# OnOnfre_dual_parafuso_ssr.net
KiCad netlist of a schematic drawn in EAGLE
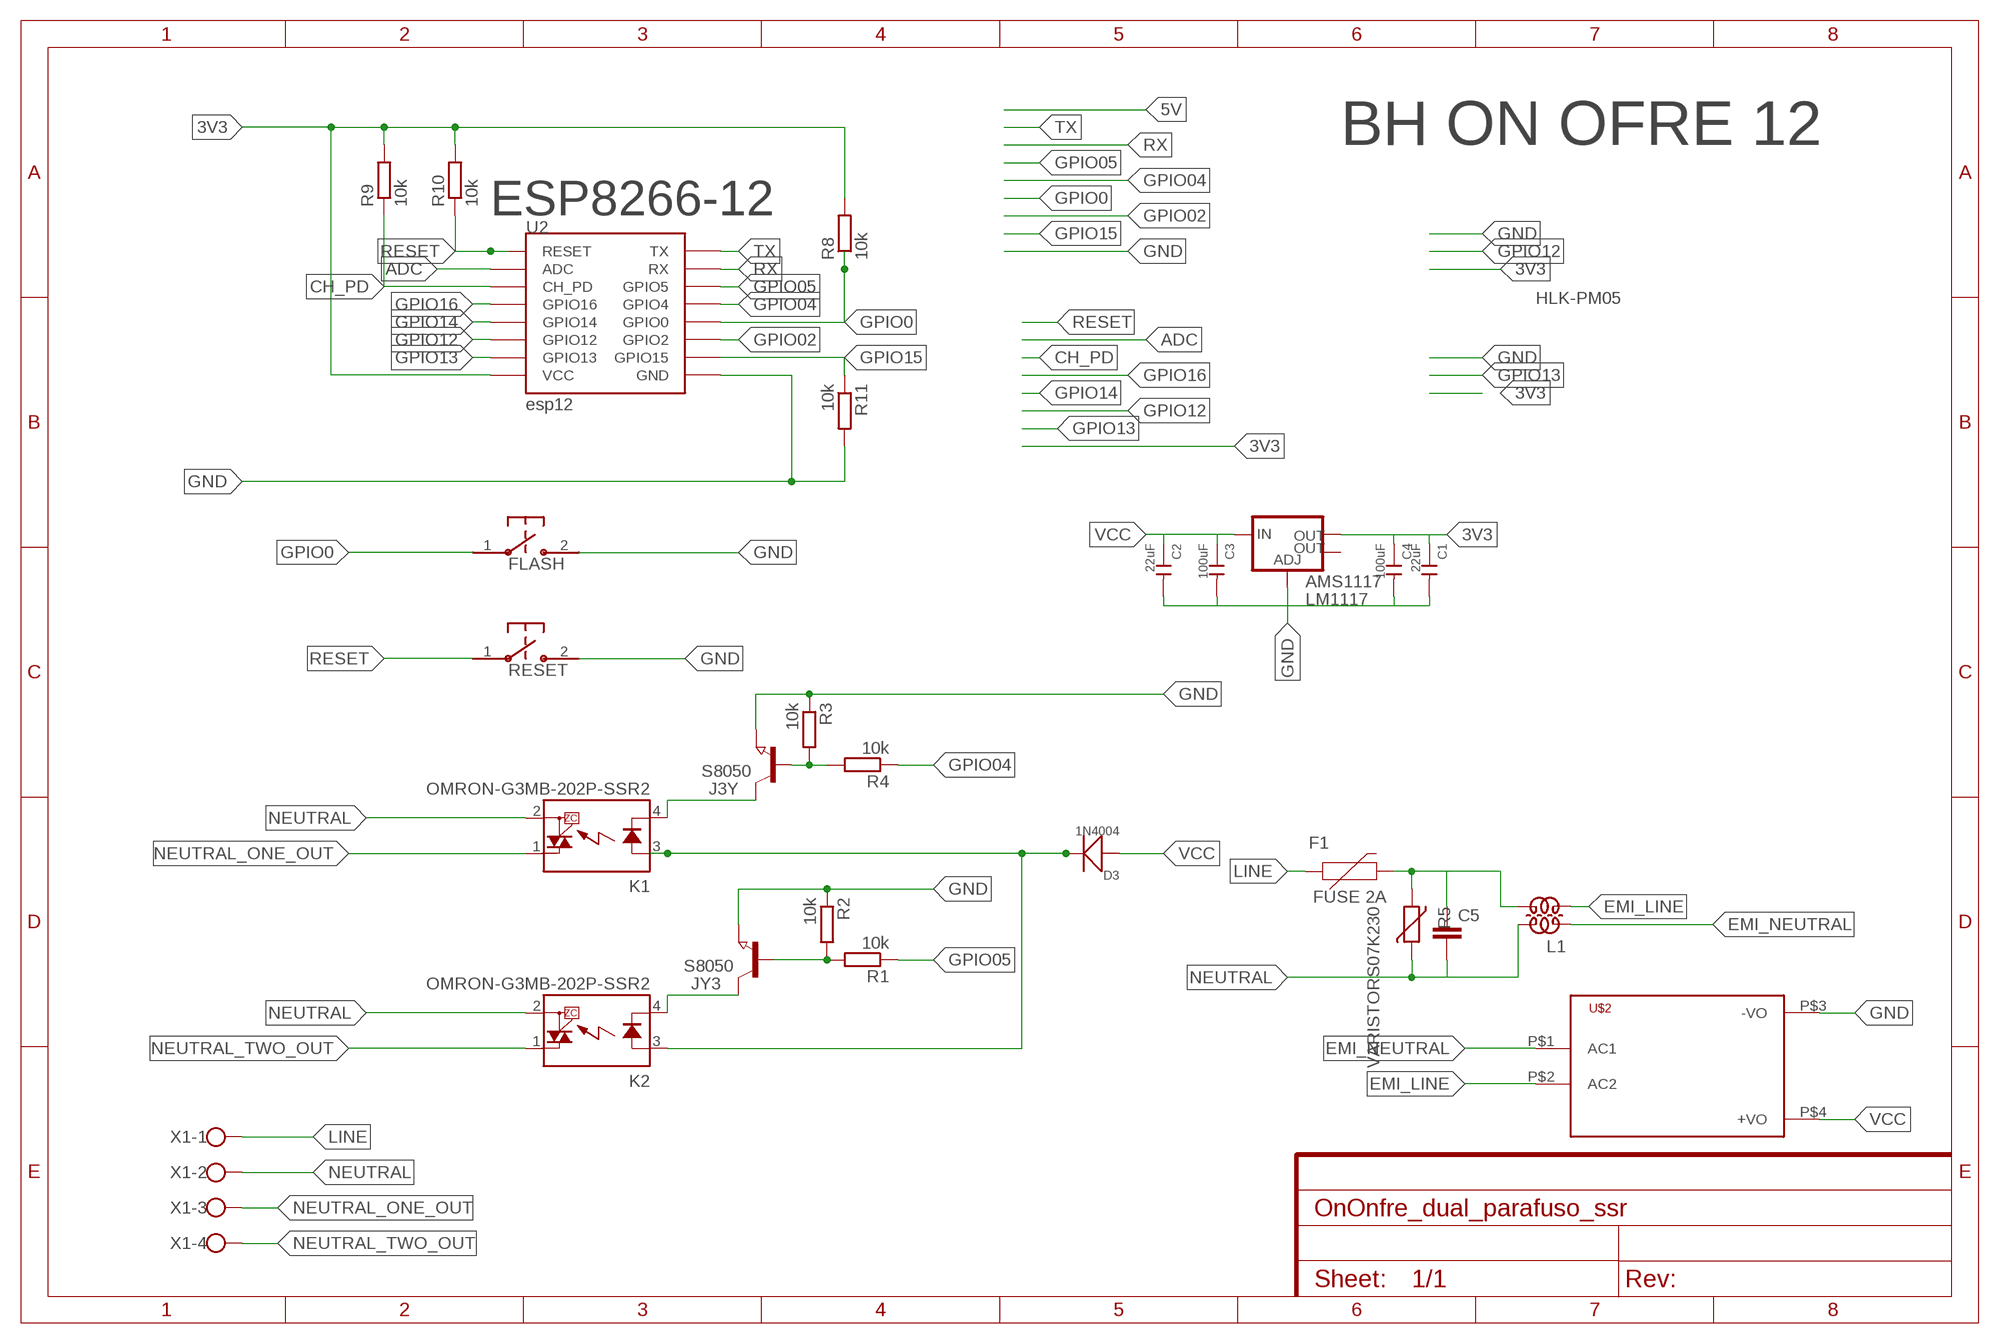
[diagram p0: schematic, sheet 1]

(export (version "E")
  (design (tool "Eeschema 10.0.6"))
  (components
    (comp (ref "AMS1117")
      (value "LM1117")
      (footprint "eagle-import:SOT223")
      (libsource (lib "eagle-import") (part "V_REG_LM1117SOT223"))
    )
    (comp (ref "C1")
      (value "22uF")
      (footprint "eagle-import:C1206")
      (fields (field (name "MPN") "CC1206KKX7RCBB102"))
      (libsource (lib "eagle-import") (part "CERAMIC-1NF-1KV-10%-X7R?(1206)"))
    )
    (comp (ref "C2")
      (value "22uF")
      (footprint "eagle-import:C1206")
      (fields (field (name "MPN") "CC1206KKX7RCBB102"))
      (libsource (lib "eagle-import") (part "CERAMIC-1NF-1KV-10%-X7R?(1206)"))
    )
    (comp (ref "C3")
      (value "100uF")
      (footprint "eagle-import:C1206")
      (fields (field (name "MPN") "CC1206KKX7RCBB102"))
      (libsource (lib "eagle-import") (part "CERAMIC-1NF-1KV-10%-X7R?(1206)"))
    )
    (comp (ref "C4")
      (value "100uF")
      (footprint "eagle-import:C1206")
      (fields (field (name "MPN") "CC1206KKX7RCBB102"))
      (libsource (lib "eagle-import") (part "CERAMIC-1NF-1KV-10%-X7R?(1206)"))
    )
    (comp (ref "C5")
      (value "C-EU102-054X133")
      (footprint "eagle-import:C102-054X133")
      (libsource (lib "eagle-import") (part "C-EU102-054X133"))
    )
    (comp (ref "D3")
      (value "1N4004")
      (footprint "eagle-import:DO-214AC")
      (fields (field (name "MPN") "1N4007"))
      (libsource (lib "eagle-import") (part "DIODE-GEN-PURPOSE-1KV-1A(DO-214AC)"))
    )
    (comp (ref "F1")
      (value "FUSE 2A")
      (footprint "eagle-import:PTH")
      (libsource (lib "eagle-import") (part "PPTC_PTH"))
    )
    (comp (ref "FLASH")
      (value "B3U-1000P-2P-SMD")
      (footprint "eagle-import:B3U-1000P")
      (fields (field (name "MANUFACTURER") "Omron") (field (name "MPN") "B3U-1000P"))
      (libsource (lib "eagle-import") (part "B3U-1000P"))
    )
    (comp (ref "J3Y")
      (value "S8050")
      (footprint "eagle-import:SOT23")
      (libsource (lib "eagle-import") (part "NPN-TRANSISTOR_SOT23"))
    )
    (comp (ref "JY3")
      (value "S8050")
      (footprint "eagle-import:SOT23")
      (libsource (lib "eagle-import") (part "NPN-TRANSISTOR_SOT23"))
    )
    (comp (ref "K1")
      (value "OMRON-G3MB-202P-SSR2")
      (footprint "eagle-import:OMRON-G3MB-202P-SSR")
      (fields (field (name "MPN") "S202S02F"))
      (libsource (lib "eagle-import") (part "OMRON-G3MB-202P-SSR2"))
    )
    (comp (ref "K2")
      (value "OMRON-G3MB-202P-SSR2")
      (footprint "eagle-import:OMRON-G3MB-202P-SSR")
      (fields (field (name "MPN") "S202S02F"))
      (libsource (lib "eagle-import") (part "OMRON-G3MB-202P-SSR2"))
    )
    (comp (ref "L1")
      (value "ZD60820510")
      (footprint "eagle-import:ZD6-2X15")
      (libsource (lib "eagle-import") (part "ZD60820510"))
    )
    (comp (ref "R1")
      (value "10k")
      (footprint "eagle-import:R0603")
      (libsource (lib "eagle-import") (part "R-EU_R0603"))
    )
    (comp (ref "R2")
      (value "10k")
      (footprint "eagle-import:R0603")
      (libsource (lib "eagle-import") (part "R-EU_R0603"))
    )
    (comp (ref "R3")
      (value "10k")
      (footprint "eagle-import:R0603")
      (libsource (lib "eagle-import") (part "R-EU_R0603"))
    )
    (comp (ref "R4")
      (value "10k")
      (footprint "eagle-import:R0603")
      (libsource (lib "eagle-import") (part "R-EU_R0603"))
    )
    (comp (ref "R5")
      (value "VARISTORS07K230")
      (footprint "eagle-import:S07K230")
      (libsource (lib "eagle-import") (part "VARISTORS07K230"))
    )
    (comp (ref "R8")
      (value "10k")
      (footprint "eagle-import:R0603")
      (libsource (lib "eagle-import") (part "R-EU_R0603"))
    )
    (comp (ref "R9")
      (value "10k")
      (footprint "eagle-import:R0603")
      (libsource (lib "eagle-import") (part "R-EU_R0603"))
    )
    (comp (ref "R10")
      (value "10k")
      (footprint "eagle-import:R0603")
      (libsource (lib "eagle-import") (part "R-EU_R0603"))
    )
    (comp (ref "R11")
      (value "10k")
      (footprint "eagle-import:R0603")
      (libsource (lib "eagle-import") (part "R-EU_R0603"))
    )
    (comp (ref "RESET")
      (value "B3U-1000P-2P-SMD")
      (footprint "eagle-import:B3U-1000P")
      (fields (field (name "MANUFACTURER") "Omron") (field (name "MPN") "B3U-1000P"))
      (libsource (lib "eagle-import") (part "B3U-1000P"))
    )
    (comp (ref "U$2")
      (value "HKLPM01")
      (footprint "eagle-import:HKLPM01")
      (libsource (lib "eagle-import") (part "HKLPM01"))
    )
    (comp (ref "U2")
      (value "esp12")
      (footprint "eagle-import:ESP12-SMD")
      (libsource (lib "eagle-import") (part "ESP12SMD"))
    )
    (comp (ref "X1")
      (value "W237-4")
      (footprint "eagle-import:W237-4")
      (libsource (lib "eagle-import") (part "W237-4"))
    )
  )
  (nets
    (net (code "1") (name "3V3") (class "Default")
      (node (ref "AMS1117") (pin "2") (pinfunction "OUT_2") (pintype "output"))
      (node (ref "C1") (pin "1") (pinfunction "1_1") (pintype "passive"))
      (node (ref "C4") (pin "1") (pinfunction "1_1") (pintype "passive"))
      (node (ref "R10") (pin "2") (pinfunction "2_2") (pintype "passive"))
      (node (ref "R8") (pin "2") (pinfunction "2_2") (pintype "passive"))
      (node (ref "R9") (pin "2") (pinfunction "2_2") (pintype "passive"))
      (node (ref "U2") (pin "VCC") (pinfunction "VCC_VCC") (pintype "bidirectional"))
    )
    (net (code "2") (name "5V") (class "Default")
      (node (ref "D3") (pin "2") (pinfunction "-_2") (pintype "passive"))
      (node (ref "K1") (pin "3") (pinfunction "A_3") (pintype "passive"))
      (node (ref "K2") (pin "3") (pinfunction "A_3") (pintype "passive"))
    )
    (net (code "3") (name "ADC") (class "Default")
      (node (ref "U2") (pin "ADC") (pinfunction "ADC_ADC") (pintype "bidirectional"))
    )
    (net (code "4") (name "CH_PD") (class "Default")
      (node (ref "R9") (pin "1") (pinfunction "1_1") (pintype "passive"))
      (node (ref "U2") (pin "CH_PD") (pinfunction "CH_PD_CH_PD") (pintype "bidirectional"))
    )
    (net (code "5") (name "EMI_LINE") (class "Default")
      (node (ref "L1") (pin "2") (pinfunction "2_2") (pintype "passive"))
      (node (ref "U$2") (pin "P$2") (pinfunction "AC2_P$2") (pintype "bidirectional"))
    )
    (net (code "6") (name "EMI_NEUTRAL") (class "Default")
      (node (ref "L1") (pin "1") (pinfunction "1_1") (pintype "passive"))
      (node (ref "U$2") (pin "P$1") (pinfunction "AC1_P$1") (pintype "bidirectional"))
    )
    (net (code "7") (name "GND") (class "Default")
      (node (ref "AMS1117") (pin "1") (pinfunction "ADJ_1") (pintype "input"))
      (node (ref "C1") (pin "2") (pinfunction "2_2") (pintype "passive"))
      (node (ref "C2") (pin "2") (pinfunction "2_2") (pintype "passive"))
      (node (ref "C3") (pin "2") (pinfunction "2_2") (pintype "passive"))
      (node (ref "C4") (pin "2") (pinfunction "2_2") (pintype "passive"))
      (node (ref "FLASH") (pin "2") (pinfunction "P$2_2") (pintype "passive"))
      (node (ref "J3Y") (pin "2") (pinfunction "E_2") (pintype "passive"))
      (node (ref "JY3") (pin "2") (pinfunction "E_2") (pintype "passive"))
      (node (ref "R11") (pin "2") (pinfunction "2_2") (pintype "passive"))
      (node (ref "R2") (pin "1") (pinfunction "1_1") (pintype "passive"))
      (node (ref "R3") (pin "1") (pinfunction "1_1") (pintype "passive"))
      (node (ref "RESET") (pin "2") (pinfunction "P$2_2") (pintype "passive"))
      (node (ref "U$2") (pin "P$3") (pinfunction "-VO_P$3") (pintype "bidirectional"))
      (node (ref "U2") (pin "GND") (pinfunction "GND_GND") (pintype "bidirectional"))
    )
    (net (code "8") (name "GPIO0") (class "Default")
      (node (ref "FLASH") (pin "1") (pinfunction "P$1_1") (pintype "passive"))
      (node (ref "R8") (pin "1") (pinfunction "1_1") (pintype "passive"))
      (node (ref "U2") (pin "GPIO0") (pinfunction "GPIO0_GPIO0") (pintype "bidirectional"))
    )
    (net (code "9") (name "GPIO02") (class "Default")
      (node (ref "U2") (pin "GPIO2") (pinfunction "GPIO2_GPIO2") (pintype "bidirectional"))
    )
    (net (code "10") (name "GPIO04") (class "Default")
      (node (ref "R4") (pin "1") (pinfunction "1_1") (pintype "passive"))
      (node (ref "U2") (pin "GPIO4") (pinfunction "GPIO4_GPIO4") (pintype "bidirectional"))
    )
    (net (code "11") (name "GPIO05") (class "Default")
      (node (ref "R1") (pin "1") (pinfunction "1_1") (pintype "passive"))
      (node (ref "U2") (pin "GPIO5") (pinfunction "GPIO5_GPIO5") (pintype "bidirectional"))
    )
    (net (code "12") (name "GPIO12") (class "Default")
      (node (ref "U2") (pin "GPIO12") (pinfunction "GPIO12_GPIO12") (pintype "bidirectional"))
    )
    (net (code "13") (name "GPIO13") (class "Default")
      (node (ref "U2") (pin "GPIO13") (pinfunction "GPIO13_GPIO13") (pintype "bidirectional"))
    )
    (net (code "14") (name "GPIO14") (class "Default")
      (node (ref "U2") (pin "GPIO14") (pinfunction "GPIO14_GPIO14") (pintype "bidirectional"))
    )
    (net (code "15") (name "GPIO15") (class "Default")
      (node (ref "R11") (pin "1") (pinfunction "1_1") (pintype "passive"))
      (node (ref "U2") (pin "GPIO15") (pinfunction "GPIO15_GPIO15") (pintype "bidirectional"))
    )
    (net (code "16") (name "GPIO16") (class "Default")
      (node (ref "U2") (pin "GPIO16") (pinfunction "GPIO16_GPIO16") (pintype "bidirectional"))
    )
    (net (code "17") (name "LINE") (class "Default")
      (node (ref "F1") (pin "P$1") (pinfunction "1_P$1") (pintype "bidirectional"))
      (node (ref "X1") (pin "1") (pinfunction "KL_1") (pintype "passive"))
    )
    (net (code "18") (name "NEUTRAL") (class "Default")
      (node (ref "C5") (pin "2") (pinfunction "2_2") (pintype "passive"))
      (node (ref "K1") (pin "2") (pinfunction "DS2_2") (pintype "passive"))
      (node (ref "K2") (pin "2") (pinfunction "DS2_2") (pintype "passive"))
      (node (ref "L1") (pin "4") (pinfunction "4_4") (pintype "passive"))
      (node (ref "R5") (pin "1") (pinfunction "1_1") (pintype "passive"))
      (node (ref "X1") (pin "2") (pinfunction "KL_2") (pintype "passive"))
    )
    (net (code "19") (name "NEUTRAL_ONE_OUT") (class "Default")
      (node (ref "K1") (pin "1") (pinfunction "DS1_1") (pintype "passive"))
      (node (ref "X1") (pin "3") (pinfunction "KL_3") (pintype "passive"))
    )
    (net (code "20") (name "NEUTRAL_TWO_OUT") (class "Default")
      (node (ref "K2") (pin "1") (pinfunction "DS1_1") (pintype "passive"))
      (node (ref "X1") (pin "4") (pinfunction "KL_4") (pintype "passive"))
    )
    (net (code "21") (name "Net-(F1-2)") (class "Default")
      (node (ref "C5") (pin "1") (pinfunction "1_1") (pintype "passive"))
      (node (ref "F1") (pin "P$2") (pinfunction "2_P$2") (pintype "bidirectional"))
      (node (ref "L1") (pin "3") (pinfunction "3_3") (pintype "passive"))
      (node (ref "R5") (pin "2") (pinfunction "2_2") (pintype "passive"))
    )
    (net (code "22") (name "Net-(J3Y-B)") (class "Default")
      (node (ref "J3Y") (pin "1") (pinfunction "B_1") (pintype "passive"))
      (node (ref "R3") (pin "2") (pinfunction "2_2") (pintype "passive"))
      (node (ref "R4") (pin "2") (pinfunction "2_2") (pintype "passive"))
    )
    (net (code "23") (name "Net-(J3Y-C)") (class "Default")
      (node (ref "J3Y") (pin "3") (pinfunction "C_3") (pintype "passive"))
      (node (ref "K1") (pin "4") (pinfunction "K_4") (pintype "passive"))
    )
    (net (code "24") (name "Net-(JY3-B)") (class "Default")
      (node (ref "JY3") (pin "1") (pinfunction "B_1") (pintype "passive"))
      (node (ref "R1") (pin "2") (pinfunction "2_2") (pintype "passive"))
      (node (ref "R2") (pin "2") (pinfunction "2_2") (pintype "passive"))
    )
    (net (code "25") (name "Net-(JY3-C)") (class "Default")
      (node (ref "JY3") (pin "3") (pinfunction "C_3") (pintype "passive"))
      (node (ref "K2") (pin "4") (pinfunction "K_4") (pintype "passive"))
    )
    (net (code "26") (name "RESET") (class "Default")
      (node (ref "R10") (pin "1") (pinfunction "1_1") (pintype "passive"))
      (node (ref "RESET") (pin "1") (pinfunction "P$1_1") (pintype "passive"))
      (node (ref "U2") (pin "RESET") (pinfunction "RESET_RESET") (pintype "bidirectional"))
    )
    (net (code "27") (name "RX") (class "Default")
      (node (ref "U2") (pin "RXD0") (pinfunction "RX_RXD0") (pintype "bidirectional"))
    )
    (net (code "28") (name "TX") (class "Default")
      (node (ref "U2") (pin "TXD0") (pinfunction "TX_TXD0") (pintype "bidirectional"))
    )
    (net (code "29") (name "VCC") (class "Default")
      (node (ref "AMS1117") (pin "3") (pinfunction "IN_3") (pintype "input"))
      (node (ref "C2") (pin "1") (pinfunction "1_1") (pintype "passive"))
      (node (ref "C3") (pin "1") (pinfunction "1_1") (pintype "passive"))
      (node (ref "D3") (pin "1") (pinfunction "+_1") (pintype "passive"))
      (node (ref "U$2") (pin "P$4") (pinfunction "+VO_P$4") (pintype "bidirectional"))
    )
    (net (code "30") (name "unconnected-(AMS1117-OUT-Pad4)") (class "Default")
      (node (ref "AMS1117") (pin "4") (pinfunction "OUT_4") (pintype "output"))
    )
  )
)
